# ospi150.net
KiCad netlist of a schematic drawn in EAGLE
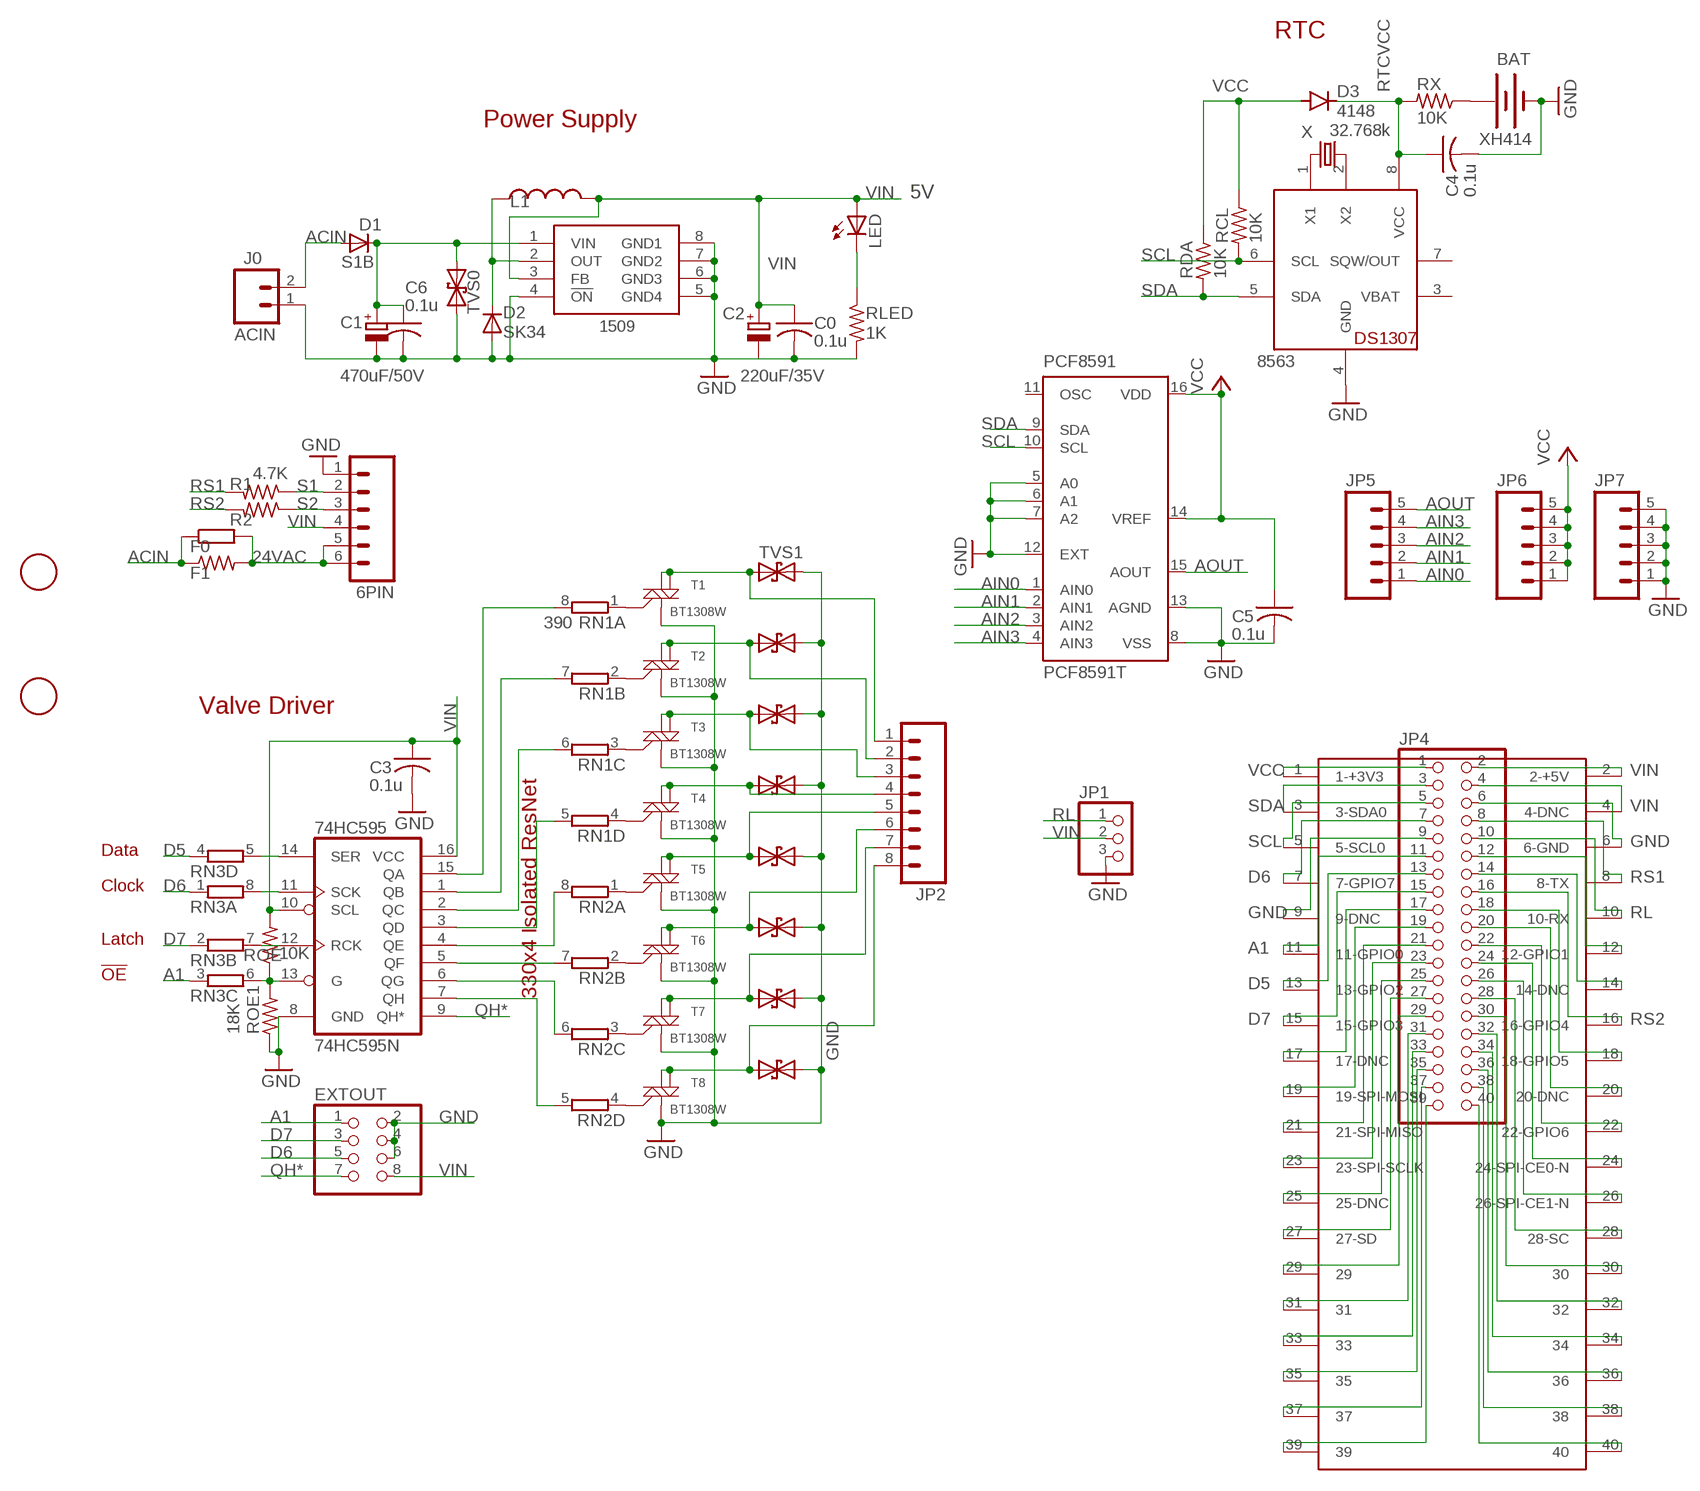
[diagram p0: schematic, sheet 1]

(export (version "E")
  (design (tool "Eeschema 10.0.6"))
  (components
    (comp (ref "1F")
      (value "FIDUCIAL")
      (footprint "eagle-import:FIDUCIAL_1MM")
      (libsource (lib "eagle-import") (part "FIDUCIAL"))
    )
    (comp (ref "2F")
      (value "FIDUCIAL")
      (footprint "eagle-import:FIDUCIAL_1MM")
      (libsource (lib "eagle-import") (part "FIDUCIAL"))
    )
    (comp (ref "6PIN")
      (value "M065MM")
      (footprint "eagle-import:SCREWTERMINAL-5MM-6")
      (libsource (lib "eagle-import") (part "M065MM"))
    )
    (comp (ref "74HC595")
      (value "74HC595N")
      (footprint "eagle-import:SO16")
      (libsource (lib "eagle-import") (part "74595DLS"))
    )
    (comp (ref "1509")
      (value "XL1509")
      (footprint "eagle-import:SO08")
      (libsource (lib "eagle-import") (part "XL1509"))
    )
    (comp (ref "8563")
      (value "PCF8563")
      (footprint "eagle-import:SO08")
      (libsource (lib "eagle-import") (part "DS1307SOIC"))
    )
    (comp (ref "BAT")
      (value "XH414")
      (footprint "eagle-import:BATTCON_XH414")
      (libsource (lib "eagle-import") (part "BATTERYXH414"))
    )
    (comp (ref "C0")
      (value "0.1u")
      (footprint "eagle-import:C0603K")
      (libsource (lib "eagle-import") (part "C-USC0603K"))
    )
    (comp (ref "C1")
      (value "470uF/50V")
      (footprint "eagle-import:E5-10,5")
      (libsource (lib "eagle-import") (part "CPOL-EUE5-10.5"))
    )
    (comp (ref "C2")
      (value "220uF/35V")
      (footprint "eagle-import:E3,5-8")
      (libsource (lib "eagle-import") (part "CPOL-EUE3.5-8"))
    )
    (comp (ref "C3")
      (value "0.1u")
      (footprint "eagle-import:C0603K")
      (libsource (lib "eagle-import") (part "C-USC0603K"))
    )
    (comp (ref "C4")
      (value "0.1u")
      (footprint "eagle-import:C0603K")
      (libsource (lib "eagle-import") (part "C-USC0603K"))
    )
    (comp (ref "C5")
      (value "0.1u")
      (footprint "eagle-import:C0603K")
      (libsource (lib "eagle-import") (part "C-USC0603K"))
    )
    (comp (ref "C6")
      (value "0.1u")
      (footprint "eagle-import:C0603K")
      (libsource (lib "eagle-import") (part "C-USC0603K"))
    )
    (comp (ref "D1")
      (value "S1B")
      (footprint "eagle-import:DO-214AC")
      (libsource (lib "eagle-import") (part "DIODE-DO-214AC"))
    )
    (comp (ref "D2")
      (value "SK34")
      (footprint "eagle-import:SMB")
      (libsource (lib "eagle-import") (part "DIODE-SMB"))
    )
    (comp (ref "D3")
      (value "4148")
      (footprint "eagle-import:MINIMELF")
      (libsource (lib "eagle-import") (part "diode@1_DIODE-MINIMELF"))
    )
    (comp (ref "EXTOUT")
      (value "PINHD-2X4/90")
      (footprint "eagle-import:2X04_90")
      (libsource (lib "eagle-import") (part "PINHD-2X4/90"))
    )
    (comp (ref "F0")
      (value "R-EU_0207/15")
      (footprint "eagle-import:0207_15")
      (libsource (lib "eagle-import") (part "R-EU_0207/15"))
    )
    (comp (ref "F1")
      (value "R-US_R1206")
      (footprint "eagle-import:R1206")
      (libsource (lib "eagle-import") (part "R-US_R1206"))
    )
    (comp (ref "J0")
      (value "ACIN")
      (footprint "eagle-import:SCREWTERMINAL-4MM-2-X")
      (libsource (lib "eagle-import") (part "M024MM-X"))
    )
    (comp (ref "JP1")
      (value "PINHD-1X3")
      (footprint "eagle-import:1X03")
      (libsource (lib "eagle-import") (part "PINHD-1X3"))
    )
    (comp (ref "JP2")
      (value "M085MM-8")
      (footprint "eagle-import:SCREWTERMINAL-5MM-8")
      (libsource (lib "eagle-import") (part "M085MM-8"))
    )
    (comp (ref "JP4")
      (value "PINHD-2X20")
      (footprint "eagle-import:2X20")
      (libsource (lib "eagle-import") (part "PINHD-2X20"))
    )
    (comp (ref "JP5")
      (value "M05PTH")
      (footprint "eagle-import:1X05")
      (libsource (lib "eagle-import") (part "M05PTH"))
    )
    (comp (ref "JP6")
      (value "M05PTH")
      (footprint "eagle-import:1X05")
      (libsource (lib "eagle-import") (part "M05PTH"))
    )
    (comp (ref "JP7")
      (value "M05PTH")
      (footprint "eagle-import:1X05")
      (libsource (lib "eagle-import") (part "M05PTH"))
    )
    (comp (ref "L1")
      (value "150uH")
      (footprint "eagle-import:CDRH125")
      (libsource (lib "eagle-import") (part "INDUCTORPWR"))
    )
    (comp (ref "LED")
      (value "LEDCHIPLED_0805")
      (footprint "eagle-import:CHIPLED_0805")
      (libsource (lib "eagle-import") (part "LEDCHIPLED_0805"))
    )
    (comp (ref "PCF8591")
      (value "PCF8591T")
      (footprint "eagle-import:SO16W")
      (fields (field (name "MPN") "PCF8591T/2,512"))
      (libsource (lib "eagle-import") (part "PCF8591T"))
    )
    (comp (ref "R1")
      (value "4.7K")
      (footprint "eagle-import:R0603")
      (libsource (lib "eagle-import") (part "adafruit2013_R-US_R0603"))
    )
    (comp (ref "R2")
      (value "4.7K")
      (footprint "eagle-import:R0603")
      (libsource (lib "eagle-import") (part "adafruit2013_R-US_R0603"))
    )
    (comp (ref "RCL")
      (value "10K")
      (footprint "eagle-import:R0603")
      (libsource (lib "eagle-import") (part "adafruit2013_R-US_R0603"))
    )
    (comp (ref "RDA")
      (value "10K")
      (footprint "eagle-import:R0603")
      (libsource (lib "eagle-import") (part "adafruit2013_R-US_R0603"))
    )
    (comp (ref "RLED")
      (value "1K")
      (footprint "eagle-import:R0603")
      (libsource (lib "eagle-import") (part "adafruit2013_R-US_R0603"))
    )
    (comp (ref "RN1")
      (value "390")
      (footprint "eagle-import:EXB38V")
      (libsource (lib "eagle-import") (part "4R-NEXB38V"))
    )
    (comp (ref "RN2")
      (value "390")
      (footprint "eagle-import:EXB38V")
      (libsource (lib "eagle-import") (part "4R-NEXB38V"))
    )
    (comp (ref "RN3")
      (value "390")
      (footprint "eagle-import:EXB38V")
      (libsource (lib "eagle-import") (part "4R-NEXB38V"))
    )
    (comp (ref "ROE")
      (value "10K")
      (footprint "eagle-import:R0603")
      (libsource (lib "eagle-import") (part "adafruit2013_R-US_R0603"))
    )
    (comp (ref "ROE1")
      (value "18K")
      (footprint "eagle-import:R0603")
      (libsource (lib "eagle-import") (part "adafruit2013_R-US_R0603"))
    )
    (comp (ref "RX")
      (value "10K")
      (footprint "eagle-import:R0603")
      (libsource (lib "eagle-import") (part "adafruit2013_R-US_R0603"))
    )
    (comp (ref "T1")
      (value "BT1308W")
      (footprint "eagle-import:SOT223")
      (libsource (lib "eagle-import") (part "MAC97SOT223"))
    )
    (comp (ref "T2")
      (value "BT1308W")
      (footprint "eagle-import:SOT223")
      (libsource (lib "eagle-import") (part "MAC97SOT223"))
    )
    (comp (ref "T3")
      (value "BT1308W")
      (footprint "eagle-import:SOT223")
      (libsource (lib "eagle-import") (part "MAC97SOT223"))
    )
    (comp (ref "T4")
      (value "BT1308W")
      (footprint "eagle-import:SOT223")
      (libsource (lib "eagle-import") (part "MAC97SOT223"))
    )
    (comp (ref "T5")
      (value "BT1308W")
      (footprint "eagle-import:SOT223")
      (libsource (lib "eagle-import") (part "MAC97SOT223"))
    )
    (comp (ref "T6")
      (value "BT1308W")
      (footprint "eagle-import:SOT223")
      (libsource (lib "eagle-import") (part "MAC97SOT223"))
    )
    (comp (ref "T7")
      (value "BT1308W")
      (footprint "eagle-import:SOT223")
      (libsource (lib "eagle-import") (part "MAC97SOT223"))
    )
    (comp (ref "T8")
      (value "BT1308W")
      (footprint "eagle-import:SOT223")
      (libsource (lib "eagle-import") (part "MAC97SOT223"))
    )
    (comp (ref "TVS0")
      (value "TVSSMB")
      (footprint "eagle-import:SMB")
      (libsource (lib "eagle-import") (part "TVSSMB"))
    )
    (comp (ref "TVS1")
      (value "TVSSMB")
      (footprint "eagle-import:SMB")
      (libsource (lib "eagle-import") (part "TVSSMB"))
    )
    (comp (ref "TVS2")
      (value "TVSSMB")
      (footprint "eagle-import:SMB")
      (libsource (lib "eagle-import") (part "TVSSMB"))
    )
    (comp (ref "TVS3")
      (value "TVSSMB")
      (footprint "eagle-import:SMB")
      (libsource (lib "eagle-import") (part "TVSSMB"))
    )
    (comp (ref "TVS4")
      (value "TVSSMB")
      (footprint "eagle-import:SMB")
      (libsource (lib "eagle-import") (part "TVSSMB"))
    )
    (comp (ref "TVS5")
      (value "TVSSMB")
      (footprint "eagle-import:SMB")
      (libsource (lib "eagle-import") (part "TVSSMB"))
    )
    (comp (ref "TVS6")
      (value "TVSSMB")
      (footprint "eagle-import:SMB")
      (libsource (lib "eagle-import") (part "TVSSMB"))
    )
    (comp (ref "TVS7")
      (value "TVSSMB")
      (footprint "eagle-import:SMB")
      (libsource (lib "eagle-import") (part "TVSSMB"))
    )
    (comp (ref "TVS8")
      (value "TVSSMB")
      (footprint "eagle-import:SMB")
      (libsource (lib "eagle-import") (part "TVSSMB"))
    )
    (comp (ref "U$2")
      (value "RPIB+B+")
      (footprint "eagle-import:RPIB+")
      (libsource (lib "eagle-import") (part "RPIB+B+"))
    )
    (comp (ref "X")
      (value "32.768k")
      (footprint "eagle-import:MM20SS1")
      (libsource (lib "eagle-import") (part "CRYSTALMM20SS1"))
    )
  )
  (nets
    (net (code "1") (name "/24VAC") (class "Default")
      (node (ref "6PIN") (pin "5") (pinfunction "5_5") (pintype "passive"))
      (node (ref "6PIN") (pin "6") (pinfunction "6_6") (pintype "passive"))
      (node (ref "F0") (pin "2") (pinfunction "2_2") (pintype "passive"))
      (node (ref "F1") (pin "2") (pinfunction "2_2") (pintype "passive"))
    )
    (net (code "2") (name "/A1") (class "Default")
      (node (ref "EXTOUT") (pin "1") (pinfunction "1_1") (pintype "passive"))
      (node (ref "JP4") (pin "11") (pinfunction "11_11") (pintype "passive"))
      (node (ref "RN3") (pin "3") (pinfunction "1_3") (pintype "passive"))
      (node (ref "U$2") (pin "11") (pinfunction "11-GPIO0_11") (pintype "bidirectional"))
    )
    (net (code "3") (name "/ACIN") (class "Default")
      (node (ref "D1") (pin "A") (pinfunction "A_A") (pintype "passive"))
      (node (ref "F0") (pin "1") (pinfunction "1_1") (pintype "passive"))
      (node (ref "F1") (pin "1") (pinfunction "1_1") (pintype "passive"))
      (node (ref "J0") (pin "2") (pinfunction "2_2") (pintype "passive"))
    )
    (net (code "4") (name "/AIN0") (class "Default")
      (node (ref "JP5") (pin "1") (pinfunction "1_1") (pintype "passive"))
      (node (ref "PCF8591") (pin "1") (pinfunction "AIN0_1") (pintype "input"))
    )
    (net (code "5") (name "/AIN1") (class "Default")
      (node (ref "JP5") (pin "2") (pinfunction "2_2") (pintype "passive"))
      (node (ref "PCF8591") (pin "2") (pinfunction "AIN1_2") (pintype "input"))
    )
    (net (code "6") (name "/AIN2") (class "Default")
      (node (ref "JP5") (pin "3") (pinfunction "3_3") (pintype "passive"))
      (node (ref "PCF8591") (pin "3") (pinfunction "AIN2_3") (pintype "input"))
    )
    (net (code "7") (name "/AIN3") (class "Default")
      (node (ref "JP5") (pin "4") (pinfunction "4_4") (pintype "passive"))
      (node (ref "PCF8591") (pin "4") (pinfunction "AIN3_4") (pintype "input"))
    )
    (net (code "8") (name "/AOUT") (class "Default")
      (node (ref "JP5") (pin "5") (pinfunction "5_5") (pintype "passive"))
      (node (ref "PCF8591") (pin "15") (pinfunction "AOUT_15") (pintype "output"))
    )
    (net (code "9") (name "/D5") (class "Default")
      (node (ref "JP4") (pin "13") (pinfunction "13_13") (pintype "passive"))
      (node (ref "RN3") (pin "4") (pinfunction "1_4") (pintype "passive"))
      (node (ref "U$2") (pin "13") (pinfunction "13-GPIO2_13") (pintype "bidirectional"))
    )
    (net (code "10") (name "/D6") (class "Default")
      (node (ref "EXTOUT") (pin "5") (pinfunction "5_5") (pintype "passive"))
      (node (ref "JP4") (pin "7") (pinfunction "7_7") (pintype "passive"))
      (node (ref "RN3") (pin "1") (pinfunction "1_1") (pintype "passive"))
      (node (ref "U$2") (pin "7") (pinfunction "7-GPIO7_7") (pintype "bidirectional"))
    )
    (net (code "11") (name "/D7") (class "Default")
      (node (ref "EXTOUT") (pin "3") (pinfunction "3_3") (pintype "passive"))
      (node (ref "JP4") (pin "15") (pinfunction "15_15") (pintype "passive"))
      (node (ref "RN3") (pin "2") (pinfunction "1_2") (pintype "passive"))
      (node (ref "U$2") (pin "15") (pinfunction "15-GPIO3_15") (pintype "bidirectional"))
    )
    (net (code "12") (name "/QH*") (class "Default")
      (node (ref "74HC595") (pin "9") (pinfunction "QH*_9") (pintype "tri_state"))
      (node (ref "EXTOUT") (pin "7") (pinfunction "7_7") (pintype "passive"))
    )
    (net (code "13") (name "/RL") (class "Default")
      (node (ref "JP1") (pin "1") (pinfunction "1_1") (pintype "passive"))
      (node (ref "JP4") (pin "10") (pinfunction "10_10") (pintype "passive"))
      (node (ref "U$2") (pin "10") (pinfunction "10-RX_10") (pintype "bidirectional"))
    )
    (net (code "14") (name "/RS1") (class "Default")
      (node (ref "JP4") (pin "8") (pinfunction "8_8") (pintype "passive"))
      (node (ref "R1") (pin "2") (pinfunction "2_2") (pintype "passive"))
      (node (ref "U$2") (pin "8") (pinfunction "8-TX_8") (pintype "bidirectional"))
    )
    (net (code "15") (name "/RS2") (class "Default")
      (node (ref "JP4") (pin "16") (pinfunction "16_16") (pintype "passive"))
      (node (ref "R2") (pin "2") (pinfunction "2_2") (pintype "passive"))
      (node (ref "U$2") (pin "16") (pinfunction "16-GPIO4_16") (pintype "bidirectional"))
    )
    (net (code "16") (name "/RTCVCC") (class "Default")
      (node (ref "8563") (pin "8") (pinfunction "VCC_8") (pintype "power_in"))
      (node (ref "C4") (pin "1") (pinfunction "1_1") (pintype "passive"))
      (node (ref "D3") (pin "C") (pinfunction "C_C") (pintype "passive"))
      (node (ref "RX") (pin "2") (pinfunction "2_2") (pintype "passive"))
    )
    (net (code "17") (name "/S1") (class "Default")
      (node (ref "6PIN") (pin "2") (pinfunction "2_2") (pintype "passive"))
      (node (ref "R1") (pin "1") (pinfunction "1_1") (pintype "passive"))
    )
    (net (code "18") (name "/S2") (class "Default")
      (node (ref "6PIN") (pin "3") (pinfunction "3_3") (pintype "passive"))
      (node (ref "R2") (pin "1") (pinfunction "1_1") (pintype "passive"))
    )
    (net (code "19") (name "/SCL") (class "Default")
      (node (ref "8563") (pin "6") (pinfunction "SCL_6") (pintype "bidirectional"))
      (node (ref "JP4") (pin "5") (pinfunction "5_5") (pintype "passive"))
      (node (ref "PCF8591") (pin "10") (pinfunction "SCL_10") (pintype "input"))
      (node (ref "RCL") (pin "2") (pinfunction "2_2") (pintype "passive"))
      (node (ref "U$2") (pin "5") (pinfunction "5-SCL0_5") (pintype "bidirectional"))
    )
    (net (code "20") (name "/SDA") (class "Default")
      (node (ref "8563") (pin "5") (pinfunction "SDA_5") (pintype "bidirectional"))
      (node (ref "JP4") (pin "3") (pinfunction "3_3") (pintype "passive"))
      (node (ref "PCF8591") (pin "9") (pinfunction "SDA_9") (pintype "bidirectional"))
      (node (ref "RDA") (pin "2") (pinfunction "2_2") (pintype "passive"))
      (node (ref "U$2") (pin "3") (pinfunction "3-SDA0_3") (pintype "bidirectional"))
    )
    (net (code "21") (name "/VBAT") (class "Default")
      (node (ref "8563") (pin "3") (pinfunction "VBAT_3") (pintype "power_in"))
    )
    (net (code "22") (name "/VIN") (class "Default")
      (node (ref "1509") (pin "3") (pinfunction "FB_3") (pintype "input"))
      (node (ref "6PIN") (pin "4") (pinfunction "4_4") (pintype "passive"))
      (node (ref "74HC595") (pin "10") (pinfunction "SCL_10") (pintype "input"))
      (node (ref "74HC595") (pin "16") (pinfunction "VCC_16") (pintype "power_in"))
      (node (ref "C0") (pin "1") (pinfunction "1_1") (pintype "passive"))
      (node (ref "C2") (pin "+") (pinfunction "+_+") (pintype "passive"))
      (node (ref "C3") (pin "1") (pinfunction "1_1") (pintype "passive"))
      (node (ref "EXTOUT") (pin "8") (pinfunction "8_8") (pintype "passive"))
      (node (ref "JP1") (pin "2") (pinfunction "2_2") (pintype "passive"))
      (node (ref "JP4") (pin "2") (pinfunction "2_2") (pintype "passive"))
      (node (ref "JP4") (pin "4") (pinfunction "4_4") (pintype "passive"))
      (node (ref "L1") (pin "2") (pinfunction "2_2") (pintype "passive"))
      (node (ref "LED") (pin "A") (pinfunction "A_A") (pintype "passive"))
      (node (ref "ROE") (pin "2") (pinfunction "2_2") (pintype "passive"))
      (node (ref "U$2") (pin "2") (pinfunction "2-+5V_2") (pintype "bidirectional"))
      (node (ref "U$2") (pin "4") (pinfunction "4-DNC_4") (pintype "bidirectional"))
    )
    (net (code "23") (name "GND") (class "Default")
      (node (ref "1509") (pin "4") (pinfunction "~{ON}_4") (pintype "bidirectional"))
      (node (ref "1509") (pin "5") (pinfunction "GND4_5") (pintype "power_in"))
      (node (ref "1509") (pin "6") (pinfunction "GND3_6") (pintype "power_in"))
      (node (ref "1509") (pin "7") (pinfunction "GND2_7") (pintype "power_in"))
      (node (ref "1509") (pin "8") (pinfunction "GND1_8") (pintype "power_in"))
      (node (ref "6PIN") (pin "1") (pinfunction "1_1") (pintype "passive"))
      (node (ref "74HC595") (pin "8") (pinfunction "GND_8") (pintype "power_in"))
      (node (ref "8563") (pin "4") (pinfunction "GND_4") (pintype "power_in"))
      (node (ref "BAT") (pin "P$1") (pinfunction "-_P$1") (pintype "power_in"))
      (node (ref "C0") (pin "2") (pinfunction "2_2") (pintype "passive"))
      (node (ref "C1") (pin "-") (pinfunction "-_-") (pintype "passive"))
      (node (ref "C2") (pin "-") (pinfunction "-_-") (pintype "passive"))
      (node (ref "C3") (pin "2") (pinfunction "2_2") (pintype "passive"))
      (node (ref "C4") (pin "2") (pinfunction "2_2") (pintype "passive"))
      (node (ref "C5") (pin "2") (pinfunction "2_2") (pintype "passive"))
      (node (ref "C6") (pin "2") (pinfunction "2_2") (pintype "passive"))
      (node (ref "D2") (pin "A") (pinfunction "A_A") (pintype "passive"))
      (node (ref "EXTOUT") (pin "2") (pinfunction "2_2") (pintype "passive"))
      (node (ref "EXTOUT") (pin "4") (pinfunction "4_4") (pintype "passive"))
      (node (ref "EXTOUT") (pin "6") (pinfunction "6_6") (pintype "passive"))
      (node (ref "J0") (pin "1") (pinfunction "1_1") (pintype "passive"))
      (node (ref "JP1") (pin "3") (pinfunction "3_3") (pintype "passive"))
      (node (ref "JP4") (pin "6") (pinfunction "6_6") (pintype "passive"))
      (node (ref "JP4") (pin "9") (pinfunction "9_9") (pintype "passive"))
      (node (ref "JP7") (pin "1") (pinfunction "1_1") (pintype "passive"))
      (node (ref "JP7") (pin "2") (pinfunction "2_2") (pintype "passive"))
      (node (ref "JP7") (pin "3") (pinfunction "3_3") (pintype "passive"))
      (node (ref "JP7") (pin "4") (pinfunction "4_4") (pintype "passive"))
      (node (ref "JP7") (pin "5") (pinfunction "5_5") (pintype "passive"))
      (node (ref "PCF8591") (pin "12") (pinfunction "EXT_12") (pintype "input"))
      (node (ref "PCF8591") (pin "13") (pinfunction "AGND_13") (pintype "power_in"))
      (node (ref "PCF8591") (pin "5") (pinfunction "A0_5") (pintype "input"))
      (node (ref "PCF8591") (pin "6") (pinfunction "A1_6") (pintype "input"))
      (node (ref "PCF8591") (pin "7") (pinfunction "A2_7") (pintype "input"))
      (node (ref "PCF8591") (pin "8") (pinfunction "VSS_8") (pintype "power_in"))
      (node (ref "RLED") (pin "2") (pinfunction "2_2") (pintype "passive"))
      (node (ref "ROE1") (pin "1") (pinfunction "1_1") (pintype "passive"))
      (node (ref "T1") (pin "1") (pinfunction "M1_1") (pintype "bidirectional"))
      (node (ref "T2") (pin "1") (pinfunction "M1_1") (pintype "bidirectional"))
      (node (ref "T3") (pin "1") (pinfunction "M1_1") (pintype "bidirectional"))
      (node (ref "T4") (pin "1") (pinfunction "M1_1") (pintype "bidirectional"))
      (node (ref "T5") (pin "1") (pinfunction "M1_1") (pintype "bidirectional"))
      (node (ref "T6") (pin "1") (pinfunction "M1_1") (pintype "bidirectional"))
      (node (ref "T7") (pin "1") (pinfunction "M1_1") (pintype "bidirectional"))
      (node (ref "T8") (pin "1") (pinfunction "M1_1") (pintype "bidirectional"))
      (node (ref "TVS0") (pin "A") (pinfunction "A_A") (pintype "passive"))
      (node (ref "TVS1") (pin "C") (pinfunction "C_C") (pintype "passive"))
      (node (ref "TVS2") (pin "C") (pinfunction "C_C") (pintype "passive"))
      (node (ref "TVS3") (pin "C") (pinfunction "C_C") (pintype "passive"))
      (node (ref "TVS4") (pin "C") (pinfunction "C_C") (pintype "passive"))
      (node (ref "TVS5") (pin "C") (pinfunction "C_C") (pintype "passive"))
      (node (ref "TVS6") (pin "C") (pinfunction "C_C") (pintype "passive"))
      (node (ref "TVS7") (pin "C") (pinfunction "C_C") (pintype "passive"))
      (node (ref "TVS8") (pin "C") (pinfunction "C_C") (pintype "passive"))
      (node (ref "U$2") (pin "6") (pinfunction "6-GND_6") (pintype "bidirectional"))
      (node (ref "U$2") (pin "9") (pinfunction "9-DNC_9") (pintype "bidirectional"))
    )
    (net (code "24") (name "Net-(74HC595-G)") (class "Default")
      (node (ref "74HC595") (pin "13") (pinfunction "G_13") (pintype "input"))
      (node (ref "RN3") (pin "6") (pinfunction "2_6") (pintype "passive"))
      (node (ref "ROE") (pin "1") (pinfunction "1_1") (pintype "passive"))
      (node (ref "ROE1") (pin "2") (pinfunction "2_2") (pintype "passive"))
    )
    (net (code "25") (name "Net-(74HC595-QA)") (class "Default")
      (node (ref "74HC595") (pin "15") (pinfunction "QA_15") (pintype "tri_state"))
      (node (ref "RN1") (pin "8") (pinfunction "2_8") (pintype "passive"))
    )
    (net (code "26") (name "Net-(74HC595-QB)") (class "Default")
      (node (ref "74HC595") (pin "1") (pinfunction "QB_1") (pintype "tri_state"))
      (node (ref "RN1") (pin "7") (pinfunction "2_7") (pintype "passive"))
    )
    (net (code "27") (name "Net-(74HC595-QC)") (class "Default")
      (node (ref "74HC595") (pin "2") (pinfunction "QC_2") (pintype "tri_state"))
      (node (ref "RN1") (pin "6") (pinfunction "2_6") (pintype "passive"))
    )
    (net (code "28") (name "Net-(74HC595-QD)") (class "Default")
      (node (ref "74HC595") (pin "3") (pinfunction "QD_3") (pintype "tri_state"))
      (node (ref "RN1") (pin "5") (pinfunction "2_5") (pintype "passive"))
    )
    (net (code "29") (name "Net-(74HC595-QE)") (class "Default")
      (node (ref "74HC595") (pin "4") (pinfunction "QE_4") (pintype "tri_state"))
      (node (ref "RN2") (pin "8") (pinfunction "2_8") (pintype "passive"))
    )
    (net (code "30") (name "Net-(74HC595-QF)") (class "Default")
      (node (ref "74HC595") (pin "5") (pinfunction "QF_5") (pintype "tri_state"))
      (node (ref "RN2") (pin "7") (pinfunction "2_7") (pintype "passive"))
    )
    (net (code "31") (name "Net-(74HC595-QG)") (class "Default")
      (node (ref "74HC595") (pin "6") (pinfunction "QG_6") (pintype "tri_state"))
      (node (ref "RN2") (pin "6") (pinfunction "2_6") (pintype "passive"))
    )
    (net (code "32") (name "Net-(74HC595-QH)") (class "Default")
      (node (ref "74HC595") (pin "7") (pinfunction "QH_7") (pintype "tri_state"))
      (node (ref "RN2") (pin "5") (pinfunction "2_5") (pintype "passive"))
    )
    (net (code "33") (name "Net-(74HC595-RCK)") (class "Default")
      (node (ref "74HC595") (pin "12") (pinfunction "RCK_12") (pintype "input"))
      (node (ref "RN3") (pin "7") (pinfunction "2_7") (pintype "passive"))
    )
    (net (code "34") (name "Net-(74HC595-SCK)") (class "Default")
      (node (ref "74HC595") (pin "11") (pinfunction "SCK_11") (pintype "input"))
      (node (ref "RN3") (pin "8") (pinfunction "2_8") (pintype "passive"))
    )
    (net (code "35") (name "Net-(74HC595-SER)") (class "Default")
      (node (ref "74HC595") (pin "14") (pinfunction "SER_14") (pintype "input"))
      (node (ref "RN3") (pin "5") (pinfunction "2_5") (pintype "passive"))
    )
    (net (code "36") (name "Net-(1509-OUT)") (class "Default")
      (node (ref "1509") (pin "2") (pinfunction "OUT_2") (pintype "input"))
      (node (ref "D2") (pin "C") (pinfunction "C_C") (pintype "passive"))
      (node (ref "L1") (pin "1") (pinfunction "1_1") (pintype "passive"))
    )
    (net (code "37") (name "Net-(1509-VIN)") (class "Default")
      (node (ref "1509") (pin "1") (pinfunction "VIN_1") (pintype "input"))
      (node (ref "C1") (pin "+") (pinfunction "+_+") (pintype "passive"))
      (node (ref "C6") (pin "1") (pinfunction "1_1") (pintype "passive"))
      (node (ref "D1") (pin "C") (pinfunction "C_C") (pintype "passive"))
      (node (ref "TVS0") (pin "C") (pinfunction "C_C") (pintype "passive"))
    )
    (net (code "38") (name "Net-(8563-X1)") (class "Default")
      (node (ref "8563") (pin "1") (pinfunction "X1_1") (pintype "passive"))
      (node (ref "X") (pin "1") (pinfunction "1_1") (pintype "passive"))
    )
    (net (code "39") (name "Net-(8563-X2)") (class "Default")
      (node (ref "8563") (pin "2") (pinfunction "X2_2") (pintype "passive"))
      (node (ref "X") (pin "4") (pinfunction "2_4") (pintype "passive"))
    )
    (net (code "40") (name "Net-(BAT-+)") (class "Default")
      (node (ref "BAT") (pin "P$2") (pinfunction "+_P$2") (pintype "power_in"))
      (node (ref "RX") (pin "1") (pinfunction "1_1") (pintype "passive"))
    )
    (net (code "41") (name "Net-(JP4-Pad29)") (class "Default")
      (node (ref "JP4") (pin "29") (pinfunction "29_29") (pintype "passive"))
      (node (ref "U$2") (pin "29") (pinfunction "29_29") (pintype "bidirectional"))
    )
    (net (code "42") (name "Net-(JP4-Pad30)") (class "Default")
      (node (ref "JP4") (pin "30") (pinfunction "30_30") (pintype "passive"))
      (node (ref "U$2") (pin "30") (pinfunction "30_30") (pintype "bidirectional"))
    )
    (net (code "43") (name "Net-(JP4-Pad31)") (class "Default")
      (node (ref "JP4") (pin "31") (pinfunction "31_31") (pintype "passive"))
      (node (ref "U$2") (pin "31") (pinfunction "31_31") (pintype "bidirectional"))
    )
    (net (code "44") (name "Net-(JP4-Pad32)") (class "Default")
      (node (ref "JP4") (pin "32") (pinfunction "32_32") (pintype "passive"))
      (node (ref "U$2") (pin "32") (pinfunction "32_32") (pintype "bidirectional"))
    )
    (net (code "45") (name "Net-(JP4-Pad33)") (class "Default")
      (node (ref "JP4") (pin "33") (pinfunction "33_33") (pintype "passive"))
      (node (ref "U$2") (pin "33") (pinfunction "33_33") (pintype "bidirectional"))
    )
    (net (code "46") (name "Net-(JP4-Pad34)") (class "Default")
      (node (ref "JP4") (pin "34") (pinfunction "34_34") (pintype "passive"))
      (node (ref "U$2") (pin "34") (pinfunction "34_34") (pintype "bidirectional"))
    )
    (net (code "47") (name "Net-(JP4-Pad35)") (class "Default")
      (node (ref "JP4") (pin "35") (pinfunction "35_35") (pintype "passive"))
      (node (ref "U$2") (pin "35") (pinfunction "35_35") (pintype "bidirectional"))
    )
    (net (code "48") (name "Net-(JP4-Pad36)") (class "Default")
      (node (ref "JP4") (pin "36") (pinfunction "36_36") (pintype "passive"))
      (node (ref "U$2") (pin "36") (pinfunction "36_36") (pintype "bidirectional"))
    )
    (net (code "49") (name "Net-(JP4-Pad37)") (class "Default")
      (node (ref "JP4") (pin "37") (pinfunction "37_37") (pintype "passive"))
      (node (ref "U$2") (pin "37") (pinfunction "37_37") (pintype "bidirectional"))
    )
    (net (code "50") (name "Net-(JP4-Pad38)") (class "Default")
      (node (ref "JP4") (pin "38") (pinfunction "38_38") (pintype "passive"))
      (node (ref "U$2") (pin "38") (pinfunction "38_38") (pintype "bidirectional"))
    )
    (net (code "51") (name "Net-(JP4-Pad39)") (class "Default")
      (node (ref "JP4") (pin "39") (pinfunction "39_39") (pintype "passive"))
      (node (ref "U$2") (pin "39") (pinfunction "39_39") (pintype "bidirectional"))
    )
    (net (code "52") (name "Net-(JP4-Pad40)") (class "Default")
      (node (ref "JP4") (pin "40") (pinfunction "40_40") (pintype "passive"))
      (node (ref "U$2") (pin "40") (pinfunction "40_40") (pintype "bidirectional"))
    )
    (net (code "53") (name "Net-(LED-PadC)") (class "Default")
      (node (ref "LED") (pin "C") (pinfunction "C_C") (pintype "passive"))
      (node (ref "RLED") (pin "1") (pinfunction "1_1") (pintype "passive"))
    )
    (net (code "54") (name "Net-(RN1B-1)") (class "Default")
      (node (ref "RN1") (pin "2") (pinfunction "1_2") (pintype "passive"))
      (node (ref "T2") (pin "3") (pinfunction "G_3") (pintype "bidirectional"))
    )
    (net (code "55") (name "Net-(RN1C-1)") (class "Default")
      (node (ref "RN1") (pin "3") (pinfunction "1_3") (pintype "passive"))
      (node (ref "T3") (pin "3") (pinfunction "G_3") (pintype "bidirectional"))
    )
    (net (code "56") (name "Net-(RN1D-1)") (class "Default")
      (node (ref "RN1") (pin "4") (pinfunction "1_4") (pintype "passive"))
      (node (ref "T4") (pin "3") (pinfunction "G_3") (pintype "bidirectional"))
    )
    (net (code "57") (name "Net-(RN2B-1)") (class "Default")
      (node (ref "RN2") (pin "2") (pinfunction "1_2") (pintype "passive"))
      (node (ref "T6") (pin "3") (pinfunction "G_3") (pintype "bidirectional"))
    )
    (net (code "58") (name "Net-(RN2C-1)") (class "Default")
      (node (ref "RN2") (pin "3") (pinfunction "1_3") (pintype "passive"))
      (node (ref "T7") (pin "3") (pinfunction "G_3") (pintype "bidirectional"))
    )
    (net (code "59") (name "Net-(RN2D-1)") (class "Default")
      (node (ref "RN2") (pin "4") (pinfunction "1_4") (pintype "passive"))
      (node (ref "T8") (pin "3") (pinfunction "G_3") (pintype "bidirectional"))
    )
    (net (code "60") (name "Net-(T1-G)") (class "Default")
      (node (ref "RN1") (pin "1") (pinfunction "1_1") (pintype "passive"))
      (node (ref "T1") (pin "3") (pinfunction "G_3") (pintype "bidirectional"))
    )
    (net (code "61") (name "Net-(T1-M2)") (class "Default")
      (node (ref "JP2") (pin "1") (pinfunction "1_1") (pintype "passive"))
      (node (ref "T1") (pin "2") (pinfunction "M2_2") (pintype "bidirectional"))
      (node (ref "T1") (pin "4") (pinfunction "M2-4_4") (pintype "bidirectional"))
      (node (ref "TVS1") (pin "A") (pinfunction "A_A") (pintype "passive"))
    )
    (net (code "62") (name "Net-(T2-M2)") (class "Default")
      (node (ref "JP2") (pin "2") (pinfunction "2_2") (pintype "passive"))
      (node (ref "T2") (pin "2") (pinfunction "M2_2") (pintype "bidirectional"))
      (node (ref "T2") (pin "4") (pinfunction "M2-4_4") (pintype "bidirectional"))
      (node (ref "TVS2") (pin "A") (pinfunction "A_A") (pintype "passive"))
    )
    (net (code "63") (name "Net-(T3-M2)") (class "Default")
      (node (ref "JP2") (pin "3") (pinfunction "3_3") (pintype "passive"))
      (node (ref "T3") (pin "2") (pinfunction "M2_2") (pintype "bidirectional"))
      (node (ref "T3") (pin "4") (pinfunction "M2-4_4") (pintype "bidirectional"))
      (node (ref "TVS3") (pin "A") (pinfunction "A_A") (pintype "passive"))
    )
    (net (code "64") (name "Net-(T4-M2)") (class "Default")
      (node (ref "JP2") (pin "4") (pinfunction "4_4") (pintype "passive"))
      (node (ref "T4") (pin "2") (pinfunction "M2_2") (pintype "bidirectional"))
      (node (ref "T4") (pin "4") (pinfunction "M2-4_4") (pintype "bidirectional"))
      (node (ref "TVS4") (pin "A") (pinfunction "A_A") (pintype "passive"))
    )
    (net (code "65") (name "Net-(T5-G)") (class "Default")
      (node (ref "RN2") (pin "1") (pinfunction "1_1") (pintype "passive"))
      (node (ref "T5") (pin "3") (pinfunction "G_3") (pintype "bidirectional"))
    )
    (net (code "66") (name "Net-(T5-M2)") (class "Default")
      (node (ref "JP2") (pin "5") (pinfunction "5_5") (pintype "passive"))
      (node (ref "T5") (pin "2") (pinfunction "M2_2") (pintype "bidirectional"))
      (node (ref "T5") (pin "4") (pinfunction "M2-4_4") (pintype "bidirectional"))
      (node (ref "TVS5") (pin "A") (pinfunction "A_A") (pintype "passive"))
    )
    (net (code "67") (name "Net-(T6-M2)") (class "Default")
      (node (ref "JP2") (pin "6") (pinfunction "6_6") (pintype "passive"))
      (node (ref "T6") (pin "2") (pinfunction "M2_2") (pintype "bidirectional"))
      (node (ref "T6") (pin "4") (pinfunction "M2-4_4") (pintype "bidirectional"))
      (node (ref "TVS6") (pin "A") (pinfunction "A_A") (pintype "passive"))
    )
    (net (code "68") (name "Net-(T7-M2)") (class "Default")
      (node (ref "JP2") (pin "7") (pinfunction "7_7") (pintype "passive"))
      (node (ref "T7") (pin "2") (pinfunction "M2_2") (pintype "bidirectional"))
      (node (ref "T7") (pin "4") (pinfunction "M2-4_4") (pintype "bidirectional"))
      (node (ref "TVS7") (pin "A") (pinfunction "A_A") (pintype "passive"))
    )
    (net (code "69") (name "Net-(T8-M2)") (class "Default")
      (node (ref "JP2") (pin "8") (pinfunction "8_8") (pintype "passive"))
      (node (ref "T8") (pin "2") (pinfunction "M2_2") (pintype "bidirectional"))
      (node (ref "T8") (pin "4") (pinfunction "M2-4_4") (pintype "bidirectional"))
      (node (ref "TVS8") (pin "A") (pinfunction "A_A") (pintype "passive"))
    )
    (net (code "70") (name "Net-(U$2-12-GPIO1)") (class "Default")
      (node (ref "JP4") (pin "12") (pinfunction "12_12") (pintype "passive"))
      (node (ref "U$2") (pin "12") (pinfunction "12-GPIO1_12") (pintype "bidirectional"))
    )
    (net (code "71") (name "Net-(U$2-14-DNC)") (class "Default")
      (node (ref "JP4") (pin "14") (pinfunction "14_14") (pintype "passive"))
      (node (ref "U$2") (pin "14") (pinfunction "14-DNC_14") (pintype "bidirectional"))
    )
    (net (code "72") (name "Net-(U$2-17-DNC)") (class "Default")
      (node (ref "JP4") (pin "17") (pinfunction "17_17") (pintype "passive"))
      (node (ref "U$2") (pin "17") (pinfunction "17-DNC_17") (pintype "bidirectional"))
    )
    (net (code "73") (name "Net-(U$2-18-GPIO5)") (class "Default")
      (node (ref "JP4") (pin "18") (pinfunction "18_18") (pintype "passive"))
      (node (ref "U$2") (pin "18") (pinfunction "18-GPIO5_18") (pintype "bidirectional"))
    )
    (net (code "74") (name "Net-(U$2-19-SPI-MOSI)") (class "Default")
      (node (ref "JP4") (pin "19") (pinfunction "19_19") (pintype "passive"))
      (node (ref "U$2") (pin "19") (pinfunction "19-SPI-MOSI_19") (pintype "bidirectional"))
    )
    (net (code "75") (name "Net-(U$2-20-DNC)") (class "Default")
      (node (ref "JP4") (pin "20") (pinfunction "20_20") (pintype "passive"))
      (node (ref "U$2") (pin "20") (pinfunction "20-DNC_20") (pintype "bidirectional"))
    )
    (net (code "76") (name "Net-(U$2-21-SPI-MISO)") (class "Default")
      (node (ref "JP4") (pin "21") (pinfunction "21_21") (pintype "passive"))
      (node (ref "U$2") (pin "21") (pinfunction "21-SPI-MISO_21") (pintype "bidirectional"))
    )
    (net (code "77") (name "Net-(U$2-22-GPIO6)") (class "Default")
      (node (ref "JP4") (pin "22") (pinfunction "22_22") (pintype "passive"))
      (node (ref "U$2") (pin "22") (pinfunction "22-GPIO6_22") (pintype "bidirectional"))
    )
    (net (code "78") (name "Net-(U$2-23-SPI-SCLK)") (class "Default")
      (node (ref "JP4") (pin "23") (pinfunction "23_23") (pintype "passive"))
      (node (ref "U$2") (pin "23") (pinfunction "23-SPI-SCLK_23") (pintype "bidirectional"))
    )
    (net (code "79") (name "Net-(U$2-24-SPI-CE0-N)") (class "Default")
      (node (ref "JP4") (pin "24") (pinfunction "24_24") (pintype "passive"))
      (node (ref "U$2") (pin "24") (pinfunction "24-SPI-CE0-N_24") (pintype "bidirectional"))
    )
    (net (code "80") (name "Net-(U$2-25-DNC)") (class "Default")
      (node (ref "JP4") (pin "25") (pinfunction "25_25") (pintype "passive"))
      (node (ref "U$2") (pin "25") (pinfunction "25-DNC_25") (pintype "bidirectional"))
    )
    (net (code "81") (name "Net-(U$2-26-SPI-CE1-N)") (class "Default")
      (node (ref "JP4") (pin "26") (pinfunction "26_26") (pintype "passive"))
      (node (ref "U$2") (pin "26") (pinfunction "26-SPI-CE1-N_26") (pintype "bidirectional"))
    )
    (net (code "82") (name "Net-(U$2-27-SD)") (class "Default")
      (node (ref "JP4") (pin "27") (pinfunction "27_27") (pintype "passive"))
      (node (ref "U$2") (pin "27") (pinfunction "27-SD_27") (pintype "bidirectional"))
    )
    (net (code "83") (name "Net-(U$2-28-SC)") (class "Default")
      (node (ref "JP4") (pin "28") (pinfunction "28_28") (pintype "passive"))
      (node (ref "U$2") (pin "28") (pinfunction "28-SC_28") (pintype "bidirectional"))
    )
    (net (code "84") (name "VCC") (class "Default")
      (node (ref "C5") (pin "1") (pinfunction "1_1") (pintype "passive"))
      (node (ref "D3") (pin "A") (pinfunction "A_A") (pintype "passive"))
      (node (ref "JP4") (pin "1") (pinfunction "1_1") (pintype "passive"))
      (node (ref "JP6") (pin "1") (pinfunction "1_1") (pintype "passive"))
      (node (ref "JP6") (pin "2") (pinfunction "2_2") (pintype "passive"))
      (node (ref "JP6") (pin "3") (pinfunction "3_3") (pintype "passive"))
      (node (ref "JP6") (pin "4") (pinfunction "4_4") (pintype "passive"))
      (node (ref "JP6") (pin "5") (pinfunction "5_5") (pintype "passive"))
      (node (ref "PCF8591") (pin "14") (pinfunction "VREF_14") (pintype "input"))
      (node (ref "PCF8591") (pin "16") (pinfunction "VDD_16") (pintype "power_in"))
      (node (ref "RCL") (pin "1") (pinfunction "1_1") (pintype "passive"))
      (node (ref "RDA") (pin "1") (pinfunction "1_1") (pintype "passive"))
      (node (ref "U$2") (pin "1") (pinfunction "1-+3V3_1") (pintype "bidirectional"))
    )
    (net (code "85") (name "unconnected-(8563-SQW{slash}OUT-Pad7)") (class "Default")
      (node (ref "8563") (pin "7") (pinfunction "SQW/OUT_7") (pintype "bidirectional"))
    )
    (net (code "86") (name "unconnected-(PCF8591-OSC-Pad11)") (class "Default")
      (node (ref "PCF8591") (pin "11") (pinfunction "OSC_11") (pintype "input"))
    )
  )
)
